# H_bridge_sch.net
KiCad netlist of a schematic drawn in Altium Designer
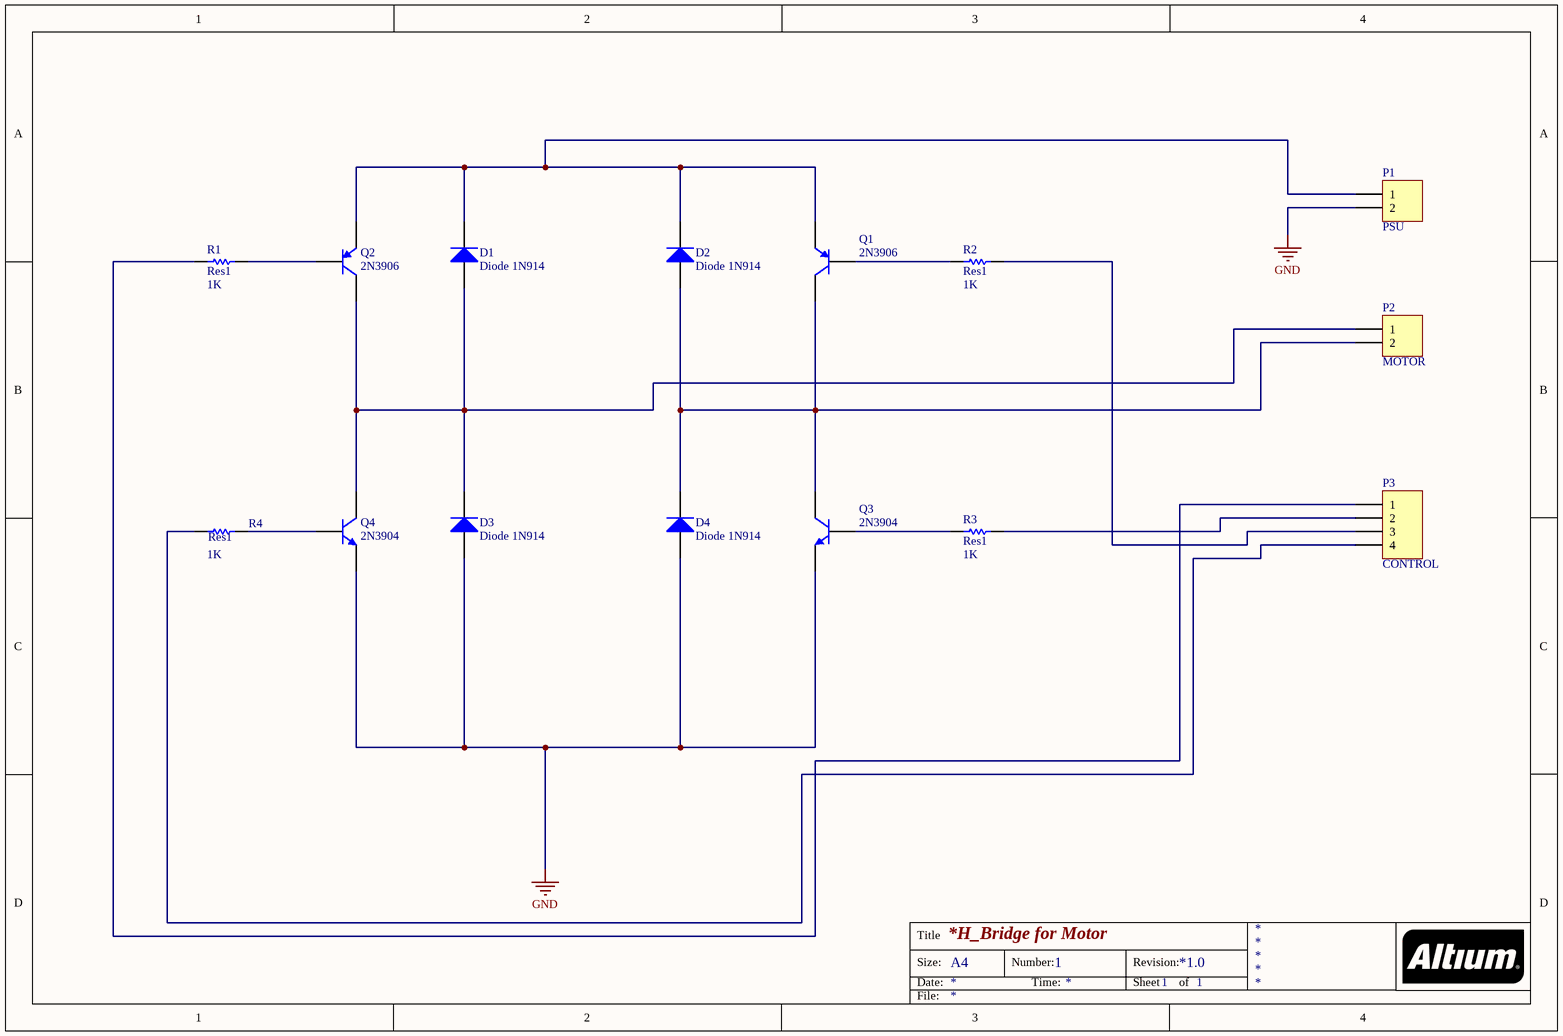
[diagram p0: H_bridge_sch.SchDoc]

(export (version "E")
  (design (tool "Eeschema 10.0.6"))
  (components
    (comp (ref "D1")
      (value "Diode 1N914")
      (footprint "DO-35")
      (description "High Conductance Fast Diode")
      (fields (field (name "PUBLISHER") "Altium Limited"))
      (libsource (lib "Miscellaneous Devices") (part "Diode 1N914"))
    )
    (comp (ref "D2")
      (value "Diode 1N914")
      (footprint "DO-35")
      (description "High Conductance Fast Diode")
      (fields (field (name "PUBLISHER") "Altium Limited"))
      (libsource (lib "Miscellaneous Devices") (part "Diode 1N914"))
    )
    (comp (ref "D3")
      (value "Diode 1N914")
      (footprint "DO-35")
      (description "High Conductance Fast Diode")
      (fields (field (name "PUBLISHER") "Altium Limited"))
      (libsource (lib "Miscellaneous Devices") (part "Diode 1N914"))
    )
    (comp (ref "D4")
      (value "Diode 1N914")
      (footprint "DO-35")
      (description "High Conductance Fast Diode")
      (fields (field (name "PUBLISHER") "Altium Limited"))
      (libsource (lib "Miscellaneous Devices") (part "Diode 1N914"))
    )
    (comp (ref "P1")
      (value "PSU")
      (footprint "HDR1X2")
      (description "Header, 2-Pin")
      (fields (field (name "PUBLISHER") "Altium Limited"))
      (libsource (lib "Miscellaneous Connectors") (part "Header 2"))
    )
    (comp (ref "P2")
      (value "MOTOR")
      (footprint "HDR1X2")
      (description "Header, 2-Pin")
      (fields (field (name "PUBLISHER") "Altium Limited"))
      (libsource (lib "Miscellaneous Connectors") (part "Header 2"))
    )
    (comp (ref "P3")
      (value "CONTROL")
      (footprint "HDR1X4")
      (description "Header, 4-Pin")
      (fields (field (name "PUBLISHER") "Altium Limited"))
      (libsource (lib "Miscellaneous Connectors") (part "Header 4"))
    )
    (comp (ref "Q1")
      (value "2N3906")
      (footprint "TO-92A")
      (description "PNP General Purpose Amplifier")
      (fields (field (name "PUBLISHER") "Altium Limited"))
      (libsource (lib "Miscellaneous Devices") (part "2N3906"))
    )
    (comp (ref "Q2")
      (value "2N3906")
      (footprint "TO-92A")
      (description "PNP General Purpose Amplifier")
      (fields (field (name "PUBLISHER") "Altium Limited"))
      (libsource (lib "Miscellaneous Devices") (part "2N3906"))
    )
    (comp (ref "Q3")
      (value "2N3904")
      (footprint "TO-92A")
      (description "NPN General Purpose Amplifier")
      (fields (field (name "PUBLISHER") "Altium Limited"))
      (libsource (lib "Miscellaneous Devices") (part "2N3904"))
    )
    (comp (ref "Q4")
      (value "2N3904")
      (footprint "TO-92A")
      (description "NPN General Purpose Amplifier")
      (fields (field (name "PUBLISHER") "Altium Limited"))
      (libsource (lib "Miscellaneous Devices") (part "2N3904"))
    )
    (comp (ref "R1")
      (value "Res1")
      (footprint "AXIAL-0.3")
      (description "Resistor")
      (fields (field (name "ALTIUM_VALUE") "1K") (field (name "PUBLISHER") "Altium Limited"))
      (libsource (lib "Miscellaneous Devices") (part "Res1"))
    )
    (comp (ref "R2")
      (value "Res1")
      (footprint "AXIAL-0.3")
      (description "Resistor")
      (fields (field (name "ALTIUM_VALUE") "1K") (field (name "PUBLISHER") "Altium Limited"))
      (libsource (lib "Miscellaneous Devices") (part "Res1"))
    )
    (comp (ref "R3")
      (value "Res1")
      (footprint "AXIAL-0.3")
      (description "Resistor")
      (fields (field (name "ALTIUM_VALUE") "1K") (field (name "PUBLISHER") "Altium Limited"))
      (libsource (lib "Miscellaneous Devices") (part "Res1"))
    )
    (comp (ref "R4")
      (value "Res1")
      (footprint "AXIAL-0.3")
      (description "Resistor")
      (fields (field (name "ALTIUM_VALUE") "1K") (field (name "PUBLISHER") "Altium Limited"))
      (libsource (lib "Miscellaneous Devices") (part "Res1"))
    )
  )
  (nets
    (net (code "1") (name "GND") (class "Default")
      (node (ref "D3") (pin "1") (pinfunction "A_1") (pintype "passive"))
      (node (ref "D4") (pin "1") (pinfunction "A_1") (pintype "passive"))
      (node (ref "P1") (pin "2") (pinfunction "2_2") (pintype "passive"))
      (node (ref "Q3") (pin "1") (pinfunction "E_1") (pintype "passive"))
      (node (ref "Q4") (pin "1") (pinfunction "E_1") (pintype "passive"))
    )
    (net (code "2") (name "Net-(D1-A)") (class "Default")
      (node (ref "D1") (pin "1") (pinfunction "A_1") (pintype "passive"))
      (node (ref "D3") (pin "2") (pinfunction "K_2") (pintype "passive"))
      (node (ref "P2") (pin "1") (pinfunction "1_1") (pintype "passive"))
      (node (ref "Q2") (pin "3") (pinfunction "C_3") (pintype "passive"))
      (node (ref "Q4") (pin "3") (pinfunction "C_3") (pintype "passive"))
    )
    (net (code "3") (name "Net-(D1-K)") (class "Default")
      (node (ref "D1") (pin "2") (pinfunction "K_2") (pintype "passive"))
      (node (ref "D2") (pin "2") (pinfunction "K_2") (pintype "passive"))
      (node (ref "P1") (pin "1") (pinfunction "1_1") (pintype "passive"))
      (node (ref "Q1") (pin "1") (pinfunction "E_1") (pintype "passive"))
      (node (ref "Q2") (pin "1") (pinfunction "E_1") (pintype "passive"))
    )
    (net (code "4") (name "Net-(D2-A)") (class "Default")
      (node (ref "D2") (pin "1") (pinfunction "A_1") (pintype "passive"))
      (node (ref "D4") (pin "2") (pinfunction "K_2") (pintype "passive"))
      (node (ref "P2") (pin "2") (pinfunction "2_2") (pintype "passive"))
      (node (ref "Q1") (pin "3") (pinfunction "C_3") (pintype "passive"))
      (node (ref "Q3") (pin "3") (pinfunction "C_3") (pintype "passive"))
    )
    (net (code "5") (name "Net-(P3-Pad1)") (class "Default")
      (node (ref "P3") (pin "1") (pinfunction "1_1") (pintype "passive"))
      (node (ref "R1") (pin "1") (pinfunction "1_1") (pintype "passive"))
    )
    (net (code "6") (name "Net-(P3-Pad2)") (class "Default")
      (node (ref "P3") (pin "2") (pinfunction "2_2") (pintype "passive"))
      (node (ref "R3") (pin "2") (pinfunction "2_2") (pintype "passive"))
    )
    (net (code "7") (name "Net-(P3-Pad3)") (class "Default")
      (node (ref "P3") (pin "3") (pinfunction "3_3") (pintype "passive"))
      (node (ref "R2") (pin "1") (pinfunction "1_1") (pintype "passive"))
    )
    (net (code "8") (name "Net-(P3-Pad4)") (class "Default")
      (node (ref "P3") (pin "4") (pinfunction "4_4") (pintype "passive"))
      (node (ref "R4") (pin "1") (pinfunction "1_1") (pintype "passive"))
    )
    (net (code "9") (name "Net-(Q1-B)") (class "Default")
      (node (ref "Q1") (pin "2") (pinfunction "B_2") (pintype "passive"))
      (node (ref "R2") (pin "2") (pinfunction "2_2") (pintype "passive"))
    )
    (net (code "10") (name "Net-(Q2-B)") (class "Default")
      (node (ref "Q2") (pin "2") (pinfunction "B_2") (pintype "passive"))
      (node (ref "R1") (pin "2") (pinfunction "2_2") (pintype "passive"))
    )
    (net (code "11") (name "Net-(Q3-B)") (class "Default")
      (node (ref "Q3") (pin "2") (pinfunction "B_2") (pintype "passive"))
      (node (ref "R3") (pin "1") (pinfunction "1_1") (pintype "passive"))
    )
    (net (code "12") (name "Net-(Q4-B)") (class "Default")
      (node (ref "Q4") (pin "2") (pinfunction "B_2") (pintype "passive"))
      (node (ref "R4") (pin "2") (pinfunction "2_2") (pintype "passive"))
    )
  )
)
